# Microcontroller.net
KiCad netlist of a schematic drawn in Altium Designer
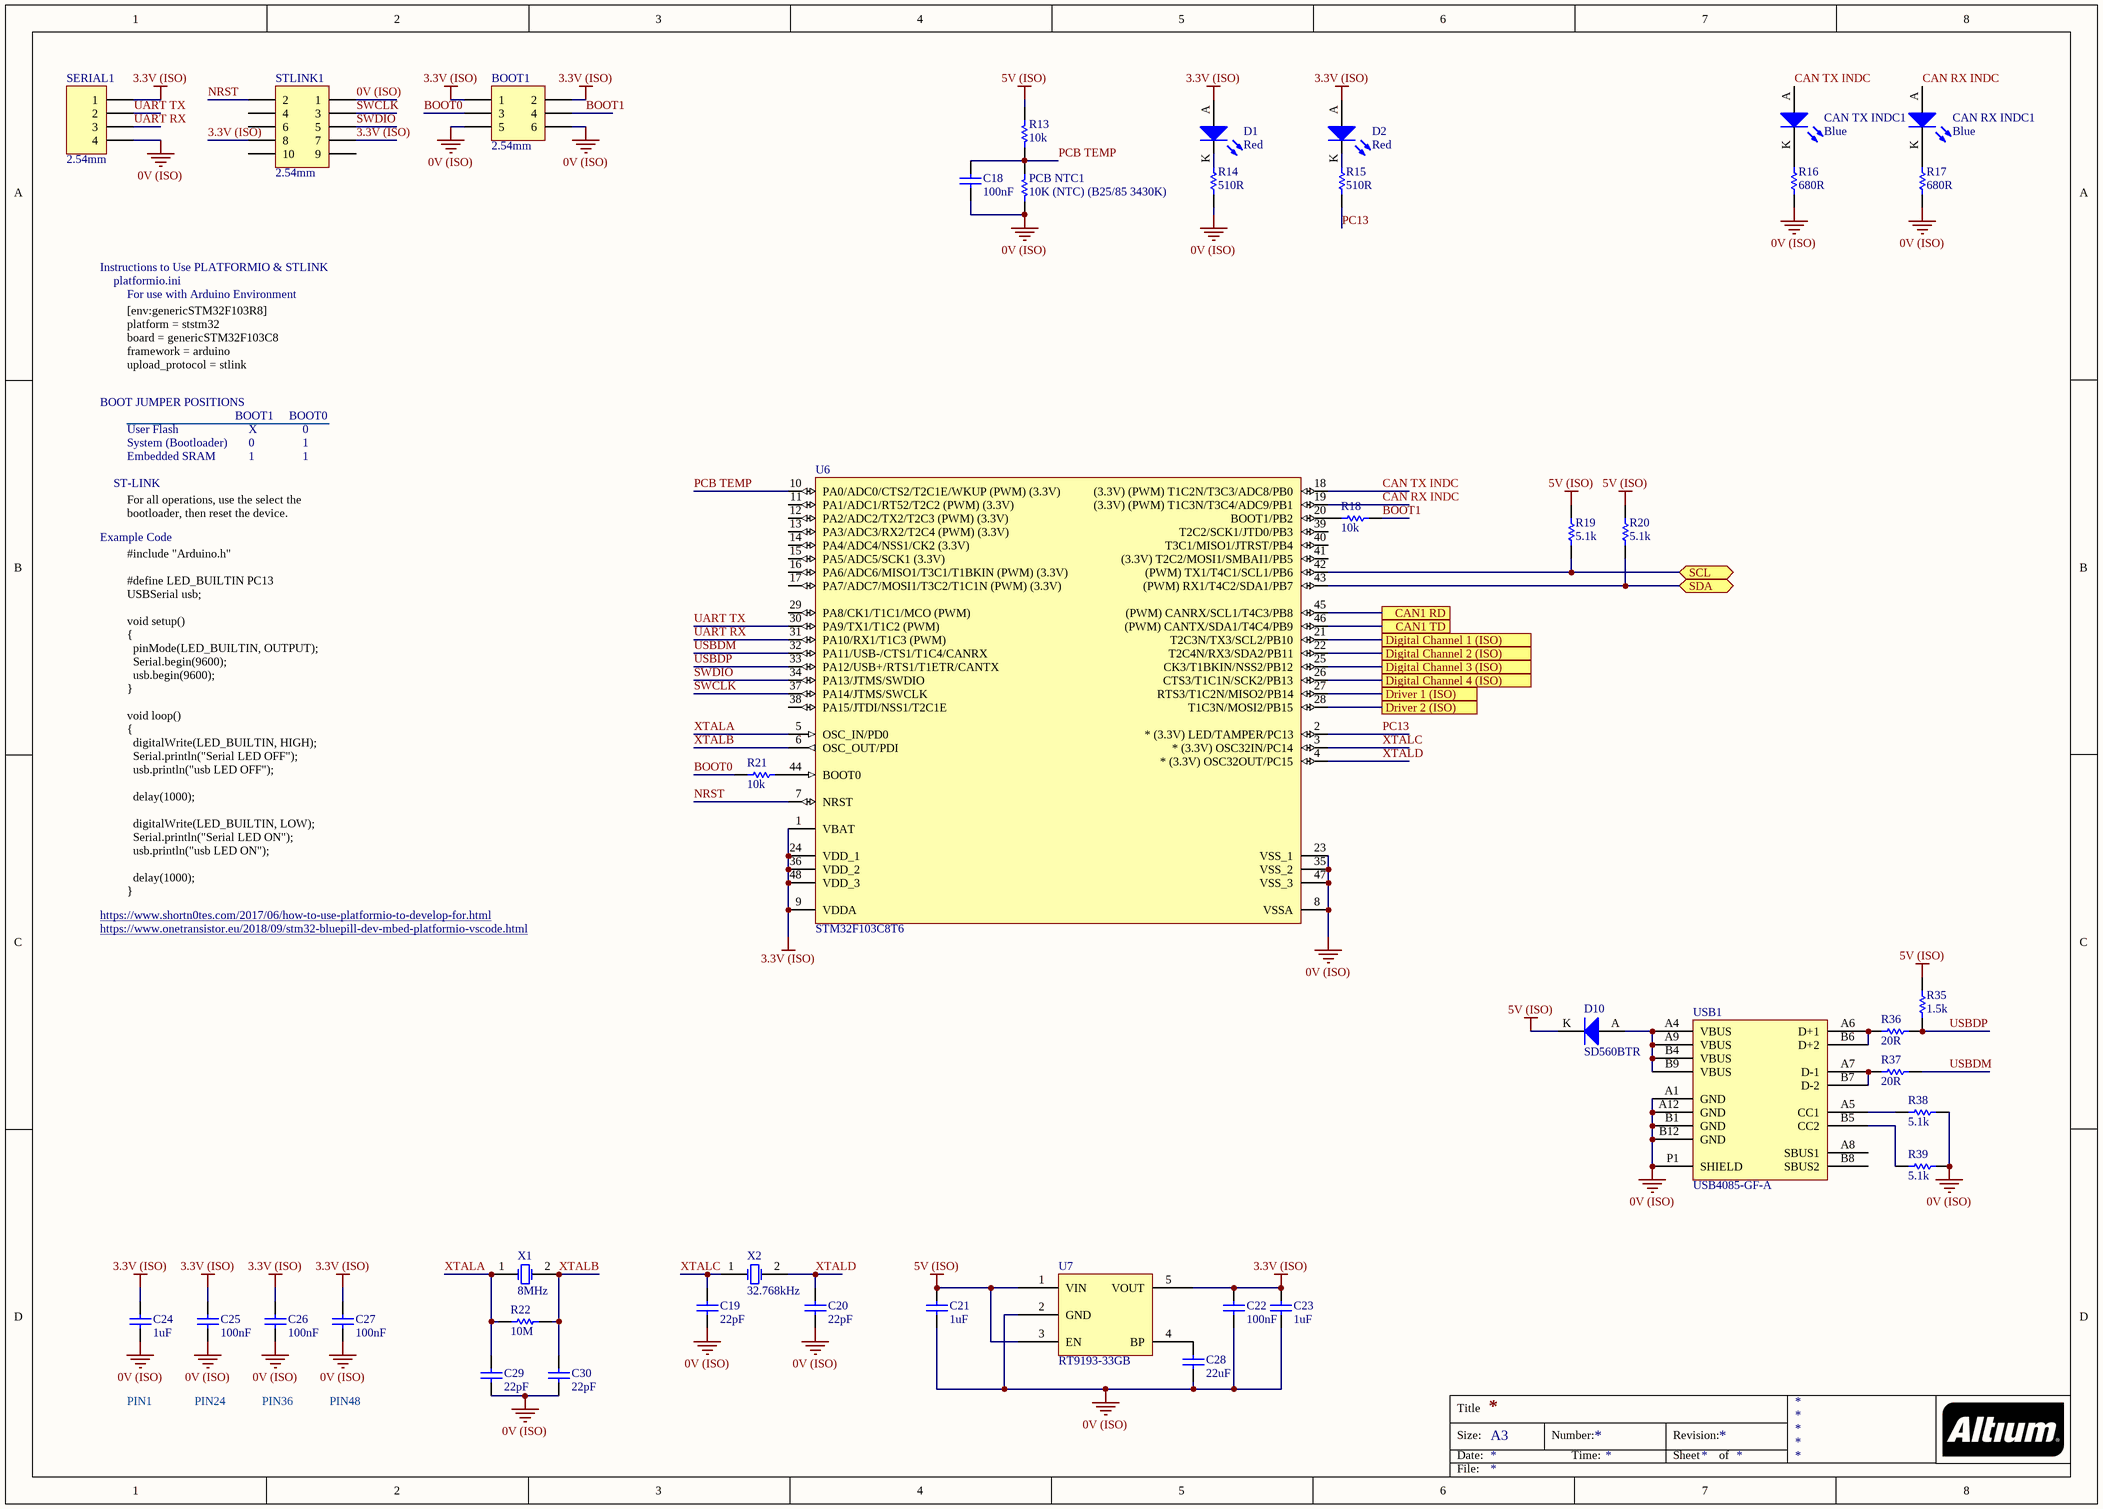
[diagram p0: Microcontroller.SchDoc]

(export (version "E")
  (design (tool "Eeschema 10.0.6"))
  (components
    (comp (ref "BOOT1")
      (value "2.54mm")
      (footprint "TH 2.54mm Header 2x3")
      (fields (field (name "PART NUMBER") "TH 2.54mm Header 2x3") (field (name "CONTACT") "NA"))
      (libsource (lib "ts_20-standard-connectors") (part "Header 2x3"))
    )
    (comp (ref "C18")
      (value "100nF")
      (footprint "0805")
      (fields
        (field (name "PART NUMBER") "GCM21BR71E104KA37L")
        (field (name "TOLERANCE") "10%")
        (field (name "MANUFACTURER") "muRata")
      )
      (libsource (lib "ts_20-standard-library") (part "Capacitor"))
    )
    (comp (ref "C19")
      (value "22pF")
      (footprint "0805")
      (fields
        (field (name "PART NUMBER") "GCM21B5C1H220JA37L")
        (field (name "TOLERANCE") "5%")
        (field (name "MANUFACTURER") "muRata")
      )
      (libsource (lib "ts_20-standard-library") (part "Capacitor"))
    )
    (comp (ref "C20")
      (value "22pF")
      (footprint "0805")
      (fields
        (field (name "PART NUMBER") "GCM21B5C1H220JA37L")
        (field (name "TOLERANCE") "5%")
        (field (name "MANUFACTURER") "muRata")
      )
      (libsource (lib "ts_20-standard-library") (part "Capacitor"))
    )
    (comp (ref "C21")
      (value "1uF")
      (footprint "0805")
      (fields
        (field (name "PART NUMBER") "AC0805KKX7R8BB105")
        (field (name "TOLERANCE") "10%")
        (field (name "MANUFACTURER") "YAGEO")
      )
      (libsource (lib "ts_20-standard-library") (part "Capacitor"))
    )
    (comp (ref "C22")
      (value "100nF")
      (footprint "0805")
      (fields
        (field (name "PART NUMBER") "GCM21BR71E104KA37L")
        (field (name "TOLERANCE") "10%")
        (field (name "MANUFACTURER") "muRata")
      )
      (libsource (lib "ts_20-standard-library") (part "Capacitor"))
    )
    (comp (ref "C23")
      (value "1uF")
      (footprint "0805")
      (fields
        (field (name "PART NUMBER") "AC0805KKX7R8BB105")
        (field (name "TOLERANCE") "10%")
        (field (name "MANUFACTURER") "YAGEO")
      )
      (libsource (lib "ts_20-standard-library") (part "Capacitor"))
    )
    (comp (ref "C24")
      (value "1uF")
      (footprint "0805")
      (fields
        (field (name "PART NUMBER") "AC0805KKX7R8BB105")
        (field (name "TOLERANCE") "10%")
        (field (name "MANUFACTURER") "YAGEO")
      )
      (libsource (lib "ts_20-standard-library") (part "Capacitor"))
    )
    (comp (ref "C25")
      (value "100nF")
      (footprint "0805")
      (fields
        (field (name "PART NUMBER") "GCM21BR71E104KA37L")
        (field (name "TOLERANCE") "10%")
        (field (name "MANUFACTURER") "muRata")
      )
      (libsource (lib "ts_20-standard-library") (part "Capacitor"))
    )
    (comp (ref "C26")
      (value "100nF")
      (footprint "0805")
      (fields
        (field (name "PART NUMBER") "GCM21BR71E104KA37L")
        (field (name "TOLERANCE") "10%")
        (field (name "MANUFACTURER") "muRata")
      )
      (libsource (lib "ts_20-standard-library") (part "Capacitor"))
    )
    (comp (ref "C27")
      (value "100nF")
      (footprint "0805")
      (fields
        (field (name "PART NUMBER") "GCM21BR71E104KA37L")
        (field (name "TOLERANCE") "10%")
        (field (name "MANUFACTURER") "muRata")
      )
      (libsource (lib "ts_20-standard-library") (part "Capacitor"))
    )
    (comp (ref "C28")
      (value "22uF")
      (footprint "0805")
      (fields
        (field (name "PART NUMBER") "GRM21BR61A226ME51L")
        (field (name "TOLERANCE") "20%")
        (field (name "MANUFACTURER") "muRata")
      )
      (libsource (lib "ts_20-standard-library") (part "Capacitor"))
    )
    (comp (ref "C29")
      (value "22pF")
      (footprint "0805")
      (fields
        (field (name "PART NUMBER") "GCM21B5C1H220JA37L")
        (field (name "TOLERANCE") "5%")
        (field (name "MANUFACTURER") "muRata")
      )
      (libsource (lib "ts_20-standard-library") (part "Capacitor"))
    )
    (comp (ref "C30")
      (value "22pF")
      (footprint "0805")
      (fields
        (field (name "PART NUMBER") "GCM21B5C1H220JA37L")
        (field (name "TOLERANCE") "5%")
        (field (name "MANUFACTURER") "muRata")
      )
      (libsource (lib "ts_20-standard-library") (part "Capacitor"))
    )
    (comp (ref "CAN RX INDC1")
      (value "Blue")
      (footprint "0805 LED")
      (description "LED BLUE CLEAR 2012 SMD")
      (fields
        (field (name "PART NUMBER") "SML-MN2BCTT86C")
        (field (name "MANUFACTURER") "ROHM Semiconductor")
      )
      (libsource (lib "ts_20-standard-library") (part "LED"))
    )
    (comp (ref "CAN TX INDC1")
      (value "Blue")
      (footprint "0805 LED")
      (description "LED BLUE CLEAR 2012 SMD")
      (fields
        (field (name "PART NUMBER") "SML-MN2BCTT86C")
        (field (name "MANUFACTURER") "ROHM Semiconductor")
      )
      (libsource (lib "ts_20-standard-library") (part "LED"))
    )
    (comp (ref "D1")
      (value "Red")
      (footprint "0805 LED")
      (description "Red LED Indication - Discrete 1.75V 0805 (2012 Metric)")
      (fields (field (name "MANUFACTURER") "ROHM Semiconductor") (field (name "PART NUMBER") "SML-210LTT86"))
      (libsource (lib "ts_20-standard-library") (part "LED"))
    )
    (comp (ref "D2")
      (value "Red")
      (footprint "0805 LED")
      (description "Red LED Indication - Discrete 1.75V 0805 (2012 Metric)")
      (fields (field (name "MANUFACTURER") "ROHM Semiconductor") (field (name "PART NUMBER") "SML-210LTT86"))
      (libsource (lib "ts_20-standard-library") (part "LED"))
    )
    (comp (ref "D10")
      (value "SD560BTR")
      (footprint "SMB Diode")
      (description "1.2V_F 600V 5A SMB")
      (fields
        (field (name "MANUFACTURER") "SMC Diode Solutions")
        (field (name "DIGIKEY PART NUMBER") "1655-1530-2-ND")
      )
      (libsource (lib "ts_20-standard-library") (part "Diode"))
    )
    (comp (ref "PCB NTC1")
      (value "10K (NTC) (B25/85 3430K)")
      (footprint "0805")
      (fields
        (field (name "PART NUMBER") "NTCS0805E3103FLT")
        (field (name "MANUFACTURER") "Vishay Beyschlag")
        (field (name "TOLERANCE") "0.01")
      )
      (libsource (lib "ts_20-standard-library") (part "Resistor"))
    )
    (comp (ref "R13")
      (value "10k")
      (footprint "0805")
      (fields
        (field (name "PART NUMBER") "RC0805FR0710KL")
        (field (name "MANUFACTURER") "YAGEO")
        (field (name "TOLERANCE") "0.01")
      )
      (libsource (lib "ts_20-standard-library") (part "Resistor"))
    )
    (comp (ref "R14")
      (value "510R")
      (footprint "0805")
      (fields
        (field (name "MANUFACTURER") "YAGEO")
        (field (name "PART NUMBER") "RC0805FR07510RL")
        (field (name "TOLERANCE") "0.01")
      )
      (libsource (lib "ts_20-standard-library") (part "Resistor"))
    )
    (comp (ref "R15")
      (value "510R")
      (footprint "0805")
      (fields
        (field (name "MANUFACTURER") "YAGEO")
        (field (name "PART NUMBER") "RC0805FR07510RL")
        (field (name "TOLERANCE") "0.01")
      )
      (libsource (lib "ts_20-standard-library") (part "Resistor"))
    )
    (comp (ref "R16")
      (value "680R")
      (footprint "0805")
      (fields
        (field (name "PART NUMBER") "RC0805FR07680RL")
        (field (name "MANUFACTURER") "YAGEO")
        (field (name "TOLERANCE") "0.01")
      )
      (libsource (lib "ts_20-standard-library") (part "Resistor"))
    )
    (comp (ref "R17")
      (value "680R")
      (footprint "0805")
      (fields
        (field (name "PART NUMBER") "RC0805FR07680RL")
        (field (name "MANUFACTURER") "YAGEO")
        (field (name "TOLERANCE") "0.01")
      )
      (libsource (lib "ts_20-standard-library") (part "Resistor"))
    )
    (comp (ref "R18")
      (value "10k")
      (footprint "0805")
      (fields
        (field (name "PART NUMBER") "RC0805FR0710KL")
        (field (name "MANUFACTURER") "YAGEO")
        (field (name "TOLERANCE") "0.01")
      )
      (libsource (lib "ts_20-standard-library") (part "Resistor"))
    )
    (comp (ref "R19")
      (value "5.1k")
      (footprint "0805")
      (fields
        (field (name "PART NUMBER") "RC0805FR075K1L")
        (field (name "MANUFACTURER") "YAGEO")
        (field (name "TOLERANCE") "0.01")
      )
      (libsource (lib "ts_20-standard-library") (part "Resistor"))
    )
    (comp (ref "R20")
      (value "5.1k")
      (footprint "0805")
      (fields
        (field (name "PART NUMBER") "RC0805FR075K1L")
        (field (name "MANUFACTURER") "YAGEO")
        (field (name "TOLERANCE") "0.01")
      )
      (libsource (lib "ts_20-standard-library") (part "Resistor"))
    )
    (comp (ref "R21")
      (value "10k")
      (footprint "0805")
      (fields
        (field (name "PART NUMBER") "RC0805FR0710KL")
        (field (name "MANUFACTURER") "YAGEO")
        (field (name "TOLERANCE") "0.01")
      )
      (libsource (lib "ts_20-standard-library") (part "Resistor"))
    )
    (comp (ref "R22")
      (value "10M")
      (footprint "0805")
      (fields
        (field (name "PART NUMBER") "RC0805FR0710ML")
        (field (name "MANUFACTURER") "YAGEO")
        (field (name "TOLERANCE") "0.01")
      )
      (libsource (lib "ts_20-standard-library") (part "Resistor"))
    )
    (comp (ref "R35")
      (value "1.5k")
      (footprint "0805")
      (fields
        (field (name "PART NUMBER") "RC0805FR071K5L")
        (field (name "MANUFACTURER") "YAGEO")
        (field (name "TOLERANCE") "0.01")
      )
      (libsource (lib "ts_20-standard-library") (part "Resistor"))
    )
    (comp (ref "R36")
      (value "20R")
      (footprint "0805")
      (fields
        (field (name "PART NUMBER") "RC0805FR0720RL")
        (field (name "MANUFACTURER") "YAGEO")
        (field (name "TOLERANCE") "0.01")
      )
      (libsource (lib "ts_20-standard-library") (part "Resistor"))
    )
    (comp (ref "R37")
      (value "20R")
      (footprint "0805")
      (fields
        (field (name "PART NUMBER") "RC0805FR0720RL")
        (field (name "MANUFACTURER") "YAGEO")
        (field (name "TOLERANCE") "0.01")
      )
      (libsource (lib "ts_20-standard-library") (part "Resistor"))
    )
    (comp (ref "R38")
      (value "5.1k")
      (footprint "0805")
      (fields
        (field (name "PART NUMBER") "RC0805FR075K1L")
        (field (name "MANUFACTURER") "YAGEO")
        (field (name "TOLERANCE") "0.01")
      )
      (libsource (lib "ts_20-standard-library") (part "Resistor"))
    )
    (comp (ref "R39")
      (value "5.1k")
      (footprint "0805")
      (fields
        (field (name "PART NUMBER") "RC0805FR075K1L")
        (field (name "MANUFACTURER") "YAGEO")
        (field (name "TOLERANCE") "0.01")
      )
      (libsource (lib "ts_20-standard-library") (part "Resistor"))
    )
    (comp (ref "SERIAL1")
      (value "2.54mm")
      (footprint "TH 2.54mm Header 1x4")
      (fields (field (name "PART NUMBER") "TH 2.54mm Header 1x4") (field (name "CONTACT") "NA"))
      (libsource (lib "ts_20-standard-connectors") (part "Header 1x4"))
    )
    (comp (ref "STLINK1")
      (value "2.54mm")
      (footprint "TH 2.54mm Header 2x5")
      (fields (field (name "PART NUMBER") "TH 2.54mm Header 2x5") (field (name "CONTACT") "NA"))
      (libsource (lib "ts_20-standard-connectors") (part "Header 2x5"))
    )
    (comp (ref "U6")
      (value "STM32F103C8T6")
      (footprint "STM 48-LQFP")
      (description "ARM® Cortex®-M3 STM32F1 Microcontroller IC 32-Bit 72MHz 64KB (64K x 8) FLASH")
      (fields
        (field (name "MANUFACTURER") "STMicroelectronics")
        (field (name "DIGIKEY PART NUMBER") "497-6063-ND")
      )
      (libsource (lib "ts_20-standard-library") (part "STM32F103C8T6"))
    )
    (comp (ref "U7")
      (value "RT9193-33GB")
      (footprint "RICHTEK SOT-23-5")
      (description "IC REG LINEAR 3.3V 300MA SOT23-5")
      (fields (field (name "MANUFACTURER") "Richtek") (field (name "DIGIKEY PART NUMBER") "1028-1014-1-ND"))
      (libsource (lib "ts_20-standard-library") (part "RT9193-33GB"))
    )
    (comp (ref "USB1")
      (value "USB4085-GF-A")
      (footprint "USB4085-GF-A")
      (description "USB - C (Type - C) USB 2.0 Receptacle Connector 16 Position Through Hole, Right Angle")
      (fields (field (name "DIGIKEY PART NUMBER") "2073-USB4085-GF-ACT-ND"))
      (libsource (lib "ts_20-standard-connectors") (part "USB4085-GF-A"))
    )
    (comp (ref "X1")
      (value "8MHz")
      (footprint "Abracon HC-49/US")
      (fields
        (field (name "PART NUMBER") "ABLS-8.000MHZ-B4-T")
        (field (name "MANUFACTURER") "Abracon LLC")
        (field (name "DIGIKEY PART NUMBER") "535-10212-2-ND")
      )
      (libsource (lib "ts_20-standard-library") (part "Crystal"))
    )
    (comp (ref "X2")
      (value "32.768kHz")
      (footprint "EPSON 2-SMD")
      (fields
        (field (name "PART NUMBER") "FC-135 32.7680KA-A5")
        (field (name "MANUFACTURER") "EPSON")
        (field (name "DIGIKEY PART NUMBER") "SER4103TR-ND")
      )
      (libsource (lib "ts_20-standard-library") (part "Crystal"))
    )
  )
  (nets
    (net (code "1") (name "/BOOT0") (class "Default")
      (node (ref "BOOT1") (pin "3") (pinfunction "3_3") (pintype "passive"))
      (node (ref "R21") (pin "1") (pinfunction "1_1") (pintype "passive"))
    )
    (net (code "2") (name "/BOOT1") (class "Default")
      (node (ref "BOOT1") (pin "4") (pinfunction "4_4") (pintype "passive"))
      (node (ref "R18") (pin "2") (pinfunction "2_2") (pintype "passive"))
    )
    (net (code "3") (name "/CAN RX INDC") (class "Default")
      (node (ref "CAN RX INDC1") (pin "A") (pinfunction "A_A") (pintype "passive"))
      (node (ref "U6") (pin "19") (pinfunction "(3.3V)_(PWM)_T1C3N/T3C4/ADC9/PB1_19") (pintype "bidirectional"))
    )
    (net (code "4") (name "/CAN TX INDC") (class "Default")
      (node (ref "CAN TX INDC1") (pin "A") (pinfunction "A_A") (pintype "passive"))
      (node (ref "U6") (pin "18") (pinfunction "(3.3V)_(PWM)_T1C2N/T3C3/ADC8/PB0_18") (pintype "bidirectional"))
    )
    (net (code "5") (name "/CAN1 RD") (class "Default")
      (node (ref "U6") (pin "45") (pinfunction "(PWM)_CANRX/SCL1/T4C3/PB8_45") (pintype "bidirectional"))
    )
    (net (code "6") (name "/CAN1 TD") (class "Default")
      (node (ref "U6") (pin "46") (pinfunction "(PWM)_CANTX/SDA1/T4C4/PB9_46") (pintype "bidirectional"))
    )
    (net (code "7") (name "/Digital Channel 1 (ISO)") (class "Default")
      (node (ref "U6") (pin "21") (pinfunction "T2C3N/TX3/SCL2/PB10_21") (pintype "bidirectional"))
    )
    (net (code "8") (name "/Digital Channel 2 (ISO)") (class "Default")
      (node (ref "U6") (pin "22") (pinfunction "T2C4N/RX3/SDA2/PB11_22") (pintype "bidirectional"))
    )
    (net (code "9") (name "/Digital Channel 3 (ISO)") (class "Default")
      (node (ref "U6") (pin "25") (pinfunction "CK3/T1BKIN/NSS2/PB12_25") (pintype "bidirectional"))
    )
    (net (code "10") (name "/Digital Channel 4 (ISO)") (class "Default")
      (node (ref "U6") (pin "26") (pinfunction "CTS3/T1C1N/SCK2/PB13_26") (pintype "bidirectional"))
    )
    (net (code "11") (name "/Driver 1 (ISO)") (class "Default")
      (node (ref "U6") (pin "27") (pinfunction "RTS3/T1C2N/MISO2/PB14_27") (pintype "bidirectional"))
    )
    (net (code "12") (name "/Driver 2 (ISO)") (class "Default")
      (node (ref "U6") (pin "28") (pinfunction "T1C3N/MOSI2/PB15_28") (pintype "bidirectional"))
    )
    (net (code "13") (name "/NRST") (class "Default")
      (node (ref "STLINK1") (pin "2") (pinfunction "2_2") (pintype "passive"))
      (node (ref "U6") (pin "7") (pinfunction "NRST_7") (pintype "bidirectional"))
    )
    (net (code "14") (name "/PC13") (class "Default")
      (node (ref "R15") (pin "1") (pinfunction "1_1") (pintype "passive"))
      (node (ref "U6") (pin "2") (pinfunction "*_(3.3V)_LED/TAMPER/PC13_2") (pintype "bidirectional"))
    )
    (net (code "15") (name "/PCB TEMP") (class "Default")
      (node (ref "C18") (pin "2") (pinfunction "2_2") (pintype "passive"))
      (node (ref "PCB NTC1") (pin "2") (pinfunction "2_2") (pintype "passive"))
      (node (ref "R13") (pin "1") (pinfunction "1_1") (pintype "passive"))
      (node (ref "U6") (pin "10") (pinfunction "PA0/ADC0/CTS2/T2C1E/WKUP_(PWM)_(3.3V)_10") (pintype "bidirectional"))
    )
    (net (code "16") (name "/SCL") (class "Default")
      (node (ref "R19") (pin "1") (pinfunction "1_1") (pintype "passive"))
      (node (ref "U6") (pin "42") (pinfunction "(PWM)_TX1/T4C1/SCL1/PB6_42") (pintype "bidirectional"))
    )
    (net (code "17") (name "/SDA") (class "Default")
      (node (ref "R20") (pin "1") (pinfunction "1_1") (pintype "passive"))
      (node (ref "U6") (pin "43") (pinfunction "(PWM)_RX1/T4C2/SDA1/PB7_43") (pintype "bidirectional"))
    )
    (net (code "18") (name "/SWCLK") (class "Default")
      (node (ref "STLINK1") (pin "3") (pinfunction "3_3") (pintype "passive"))
      (node (ref "U6") (pin "37") (pinfunction "PA14/JTMS/SWCLK_37") (pintype "bidirectional"))
    )
    (net (code "19") (name "/SWDIO") (class "Default")
      (node (ref "STLINK1") (pin "5") (pinfunction "5_5") (pintype "passive"))
      (node (ref "U6") (pin "34") (pinfunction "PA13/JTMS/SWDIO_34") (pintype "bidirectional"))
    )
    (net (code "20") (name "/UART RX") (class "Default")
      (node (ref "SERIAL1") (pin "3") (pinfunction "3_3") (pintype "passive"))
      (node (ref "U6") (pin "31") (pinfunction "PA10/RX1/T1C3_(PWM)_31") (pintype "bidirectional"))
    )
    (net (code "21") (name "/UART TX") (class "Default")
      (node (ref "SERIAL1") (pin "2") (pinfunction "2_2") (pintype "passive"))
      (node (ref "U6") (pin "30") (pinfunction "PA9/TX1/T1C2_(PWM)_30") (pintype "bidirectional"))
    )
    (net (code "22") (name "/USBDM") (class "Default")
      (node (ref "R37") (pin "2") (pinfunction "2_2") (pintype "passive"))
      (node (ref "U6") (pin "32") (pinfunction "PA11/USB-/CTS1/T1C4/CANRX_32") (pintype "bidirectional"))
    )
    (net (code "23") (name "/USBDP") (class "Default")
      (node (ref "R35") (pin "1") (pinfunction "1_1") (pintype "passive"))
      (node (ref "R36") (pin "2") (pinfunction "2_2") (pintype "passive"))
      (node (ref "U6") (pin "33") (pinfunction "PA12/USB+/RTS1/T1ETR/CANTX_33") (pintype "bidirectional"))
    )
    (net (code "24") (name "/XTALA") (class "Default")
      (node (ref "C29") (pin "2") (pinfunction "2_2") (pintype "passive"))
      (node (ref "R22") (pin "2") (pinfunction "2_2") (pintype "passive"))
      (node (ref "U6") (pin "5") (pinfunction "OSC_IN/PD0_5") (pintype "input"))
      (node (ref "X1") (pin "1") (pinfunction "OSC1_1") (pintype "passive"))
    )
    (net (code "25") (name "/XTALB") (class "Default")
      (node (ref "C30") (pin "2") (pinfunction "2_2") (pintype "passive"))
      (node (ref "R22") (pin "1") (pinfunction "1_1") (pintype "passive"))
      (node (ref "U6") (pin "6") (pinfunction "OSC_OUT/PDI_6") (pintype "output"))
      (node (ref "X1") (pin "2") (pinfunction "OSC2_2") (pintype "passive"))
    )
    (net (code "26") (name "/XTALC") (class "Default")
      (node (ref "C19") (pin "2") (pinfunction "2_2") (pintype "passive"))
      (node (ref "U6") (pin "3") (pinfunction "*_(3.3V)_OSC32IN/PC14_3") (pintype "bidirectional"))
      (node (ref "X2") (pin "1") (pinfunction "OSC1_1") (pintype "passive"))
    )
    (net (code "27") (name "/XTALD") (class "Default")
      (node (ref "C20") (pin "2") (pinfunction "2_2") (pintype "passive"))
      (node (ref "U6") (pin "4") (pinfunction "*_(3.3V)_OSC32OUT/PC15_4") (pintype "bidirectional"))
      (node (ref "X2") (pin "2") (pinfunction "OSC2_2") (pintype "passive"))
    )
    (net (code "28") (name "0V (ISO)") (class "Default")
      (node (ref "BOOT1") (pin "5") (pinfunction "5_5") (pintype "passive"))
      (node (ref "BOOT1") (pin "6") (pinfunction "6_6") (pintype "passive"))
      (node (ref "C18") (pin "1") (pinfunction "1_1") (pintype "passive"))
      (node (ref "C19") (pin "1") (pinfunction "1_1") (pintype "passive"))
      (node (ref "C20") (pin "1") (pinfunction "1_1") (pintype "passive"))
      (node (ref "C21") (pin "1") (pinfunction "1_1") (pintype "passive"))
      (node (ref "C22") (pin "1") (pinfunction "1_1") (pintype "passive"))
      (node (ref "C23") (pin "1") (pinfunction "1_1") (pintype "passive"))
      (node (ref "C24") (pin "1") (pinfunction "1_1") (pintype "passive"))
      (node (ref "C25") (pin "1") (pinfunction "1_1") (pintype "passive"))
      (node (ref "C26") (pin "1") (pinfunction "1_1") (pintype "passive"))
      (node (ref "C27") (pin "1") (pinfunction "1_1") (pintype "passive"))
      (node (ref "C28") (pin "1") (pinfunction "1_1") (pintype "passive"))
      (node (ref "C29") (pin "1") (pinfunction "1_1") (pintype "passive"))
      (node (ref "C30") (pin "1") (pinfunction "1_1") (pintype "passive"))
      (node (ref "PCB NTC1") (pin "1") (pinfunction "1_1") (pintype "passive"))
      (node (ref "R14") (pin "1") (pinfunction "1_1") (pintype "passive"))
      (node (ref "R16") (pin "1") (pinfunction "1_1") (pintype "passive"))
      (node (ref "R17") (pin "1") (pinfunction "1_1") (pintype "passive"))
      (node (ref "R38") (pin "2") (pinfunction "2_2") (pintype "passive"))
      (node (ref "R39") (pin "2") (pinfunction "2_2") (pintype "passive"))
      (node (ref "SERIAL1") (pin "4") (pinfunction "4_4") (pintype "passive"))
      (node (ref "STLINK1") (pin "1") (pinfunction "1_1") (pintype "passive"))
      (node (ref "U6") (pin "23") (pinfunction "VSS_1_23") (pintype "power_in"))
      (node (ref "U6") (pin "35") (pinfunction "VSS_2_35") (pintype "power_in"))
      (node (ref "U6") (pin "47") (pinfunction "VSS_3_47") (pintype "power_in"))
      (node (ref "U6") (pin "8") (pinfunction "VSSA_8") (pintype "power_in"))
      (node (ref "U7") (pin "2") (pinfunction "GND_2") (pintype "passive"))
      (node (ref "USB1") (pin "A1") (pinfunction "GND_A1") (pintype "passive"))
      (node (ref "USB1") (pin "A12") (pinfunction "GND_A12") (pintype "passive"))
      (node (ref "USB1") (pin "B1") (pinfunction "GND_B1") (pintype "passive"))
      (node (ref "USB1") (pin "B12") (pinfunction "GND_B12") (pintype "passive"))
      (node (ref "USB1") (pin "P1") (pinfunction "SHIELD_P1") (pintype "passive"))
    )
    (net (code "29") (name "3.3V (ISO)") (class "Default")
      (node (ref "BOOT1") (pin "1") (pinfunction "1_1") (pintype "passive"))
      (node (ref "BOOT1") (pin "2") (pinfunction "2_2") (pintype "passive"))
      (node (ref "C22") (pin "2") (pinfunction "2_2") (pintype "passive"))
      (node (ref "C23") (pin "2") (pinfunction "2_2") (pintype "passive"))
      (node (ref "C24") (pin "2") (pinfunction "2_2") (pintype "passive"))
      (node (ref "C25") (pin "2") (pinfunction "2_2") (pintype "passive"))
      (node (ref "C26") (pin "2") (pinfunction "2_2") (pintype "passive"))
      (node (ref "C27") (pin "2") (pinfunction "2_2") (pintype "passive"))
      (node (ref "D1") (pin "A") (pinfunction "A_A") (pintype "passive"))
      (node (ref "D2") (pin "A") (pinfunction "A_A") (pintype "passive"))
      (node (ref "SERIAL1") (pin "1") (pinfunction "1_1") (pintype "passive"))
      (node (ref "STLINK1") (pin "7") (pinfunction "7_7") (pintype "passive"))
      (node (ref "STLINK1") (pin "8") (pinfunction "8_8") (pintype "passive"))
      (node (ref "U6") (pin "1") (pinfunction "VBAT_1") (pintype "power_in"))
      (node (ref "U6") (pin "24") (pinfunction "VDD_1_24") (pintype "power_in"))
      (node (ref "U6") (pin "36") (pinfunction "VDD_2_36") (pintype "power_in"))
      (node (ref "U6") (pin "48") (pinfunction "VDD_3_48") (pintype "power_in"))
      (node (ref "U6") (pin "9") (pinfunction "VDDA_9") (pintype "power_in"))
      (node (ref "U7") (pin "5") (pinfunction "VOUT_5") (pintype "passive"))
    )
    (net (code "30") (name "5V (ISO)") (class "Default")
      (node (ref "C21") (pin "2") (pinfunction "2_2") (pintype "passive"))
      (node (ref "D10") (pin "K") (pinfunction "K_K") (pintype "passive"))
      (node (ref "R13") (pin "2") (pinfunction "2_2") (pintype "passive"))
      (node (ref "R19") (pin "2") (pinfunction "2_2") (pintype "passive"))
      (node (ref "R20") (pin "2") (pinfunction "2_2") (pintype "passive"))
      (node (ref "R35") (pin "2") (pinfunction "2_2") (pintype "passive"))
      (node (ref "U7") (pin "1") (pinfunction "VIN_1") (pintype "passive"))
      (node (ref "U7") (pin "3") (pinfunction "EN_3") (pintype "passive"))
    )
    (net (code "31") (name "Net-(CAN RX INDC1-PadK)") (class "Default")
      (node (ref "CAN RX INDC1") (pin "K") (pinfunction "K_K") (pintype "passive"))
      (node (ref "R17") (pin "2") (pinfunction "2_2") (pintype "passive"))
    )
    (net (code "32") (name "Net-(CAN TX INDC1-PadK)") (class "Default")
      (node (ref "CAN TX INDC1") (pin "K") (pinfunction "K_K") (pintype "passive"))
      (node (ref "R16") (pin "2") (pinfunction "2_2") (pintype "passive"))
    )
    (net (code "33") (name "Net-(D1-PadK)") (class "Default")
      (node (ref "D1") (pin "K") (pinfunction "K_K") (pintype "passive"))
      (node (ref "R14") (pin "2") (pinfunction "2_2") (pintype "passive"))
    )
    (net (code "34") (name "Net-(D2-PadK)") (class "Default")
      (node (ref "D2") (pin "K") (pinfunction "K_K") (pintype "passive"))
      (node (ref "R15") (pin "2") (pinfunction "2_2") (pintype "passive"))
    )
    (net (code "35") (name "Net-(D10-PadA)") (class "Default")
      (node (ref "D10") (pin "A") (pinfunction "A_A") (pintype "passive"))
      (node (ref "USB1") (pin "A4") (pinfunction "VBUS_A4") (pintype "passive"))
      (node (ref "USB1") (pin "A9") (pinfunction "VBUS_A9") (pintype "passive"))
      (node (ref "USB1") (pin "B4") (pinfunction "VBUS_B4") (pintype "passive"))
      (node (ref "USB1") (pin "B9") (pinfunction "VBUS_B9") (pintype "passive"))
    )
    (net (code "36") (name "Net-(U6-BOOT0)") (class "Default")
      (node (ref "R21") (pin "2") (pinfunction "2_2") (pintype "passive"))
      (node (ref "U6") (pin "44") (pinfunction "BOOT0_44") (pintype "input"))
    )
    (net (code "37") (name "Net-(U6-BOOT1{slash}PB2)") (class "Default")
      (node (ref "R18") (pin "1") (pinfunction "1_1") (pintype "passive"))
      (node (ref "U6") (pin "20") (pinfunction "BOOT1/PB2_20") (pintype "bidirectional"))
    )
    (net (code "38") (name "Net-(U7-BP)") (class "Default")
      (node (ref "C28") (pin "2") (pinfunction "2_2") (pintype "passive"))
      (node (ref "U7") (pin "4") (pinfunction "BP_4") (pintype "passive"))
    )
    (net (code "39") (name "Net-(USB1-CC1)") (class "Default")
      (node (ref "R38") (pin "1") (pinfunction "1_1") (pintype "passive"))
      (node (ref "USB1") (pin "A5") (pinfunction "CC1_A5") (pintype "passive"))
    )
    (net (code "40") (name "Net-(USB1-CC2)") (class "Default")
      (node (ref "R39") (pin "1") (pinfunction "1_1") (pintype "passive"))
      (node (ref "USB1") (pin "B5") (pinfunction "CC2_B5") (pintype "passive"))
    )
    (net (code "41") (name "Net-(USB1-D+1)") (class "Default")
      (node (ref "R36") (pin "1") (pinfunction "1_1") (pintype "passive"))
      (node (ref "USB1") (pin "A6") (pinfunction "D+1_A6") (pintype "passive"))
      (node (ref "USB1") (pin "B6") (pinfunction "D+2_B6") (pintype "passive"))
    )
    (net (code "42") (name "Net-(USB1-D-1)") (class "Default")
      (node (ref "R37") (pin "1") (pinfunction "1_1") (pintype "passive"))
      (node (ref "USB1") (pin "A7") (pinfunction "D-1_A7") (pintype "passive"))
      (node (ref "USB1") (pin "B7") (pinfunction "D-2_B7") (pintype "passive"))
    )
    (net (code "43") (name "unconnected-(STLINK1-Pad4)") (class "Default")
      (node (ref "STLINK1") (pin "4") (pinfunction "4_4") (pintype "passive"))
    )
    (net (code "44") (name "unconnected-(STLINK1-Pad6)") (class "Default")
      (node (ref "STLINK1") (pin "6") (pinfunction "6_6") (pintype "passive"))
    )
    (net (code "45") (name "unconnected-(STLINK1-Pad9)") (class "Default")
      (node (ref "STLINK1") (pin "9") (pinfunction "9_9") (pintype "passive"))
    )
    (net (code "46") (name "unconnected-(STLINK1-Pad10)") (class "Default")
      (node (ref "STLINK1") (pin "10") (pinfunction "10_10") (pintype "passive"))
    )
    (net (code "47") (name "unconnected-(U6-(3.3V)_T2C2{slash}MOSI1{slash}SMBAI1{slash}PB5-Pad41)") (class "Default")
      (node (ref "U6") (pin "41") (pinfunction "(3.3V)_T2C2/MOSI1/SMBAI1/PB5_41") (pintype "bidirectional"))
    )
    (net (code "48") (name "unconnected-(U6-PA1{slash}ADC1{slash}RT52{slash}T2C2_(PWM)_(3.3V)-Pad11)") (class "Default")
      (node (ref "U6") (pin "11") (pinfunction "PA1/ADC1/RT52/T2C2_(PWM)_(3.3V)_11") (pintype "bidirectional"))
    )
    (net (code "49") (name "unconnected-(U6-PA2{slash}ADC2{slash}TX2{slash}T2C3_(PWM)_(3.3V)-Pad12)") (class "Default")
      (node (ref "U6") (pin "12") (pinfunction "PA2/ADC2/TX2/T2C3_(PWM)_(3.3V)_12") (pintype "bidirectional"))
    )
    (net (code "50") (name "unconnected-(U6-PA3{slash}ADC3{slash}RX2{slash}T2C4_(PWM)_(3.3V)-Pad13)") (class "Default")
      (node (ref "U6") (pin "13") (pinfunction "PA3/ADC3/RX2/T2C4_(PWM)_(3.3V)_13") (pintype "bidirectional"))
    )
    (net (code "51") (name "unconnected-(U6-PA4{slash}ADC4{slash}NSS1{slash}CK2_(3.3V)-Pad14)") (class "Default")
      (node (ref "U6") (pin "14") (pinfunction "PA4/ADC4/NSS1/CK2_(3.3V)_14") (pintype "bidirectional"))
    )
    (net (code "52") (name "unconnected-(U6-PA5{slash}ADC5{slash}SCK1_(3.3V)-Pad15)") (class "Default")
      (node (ref "U6") (pin "15") (pinfunction "PA5/ADC5/SCK1_(3.3V)_15") (pintype "bidirectional"))
    )
    (net (code "53") (name "unconnected-(U6-PA6{slash}ADC6{slash}MISO1{slash}T3C1{slash}T1BKIN_(PWM)_(3.3V)-Pad16)") (class "Default")
      (node (ref "U6") (pin "16") (pinfunction "PA6/ADC6/MISO1/T3C1/T1BKIN_(PWM)_(3.3V)_16") (pintype "bidirectional"))
    )
    (net (code "54") (name "unconnected-(U6-PA7{slash}ADC7{slash}MOSI1{slash}T3C2{slash}T1C1N_(PWM)_(3.3V)-Pad17)") (class "Default")
      (node (ref "U6") (pin "17") (pinfunction "PA7/ADC7/MOSI1/T3C2/T1C1N_(PWM)_(3.3V)_17") (pintype "bidirectional"))
    )
    (net (code "55") (name "unconnected-(U6-PA8{slash}CK1{slash}T1C1{slash}MCO_(PWM)-Pad29)") (class "Default")
      (node (ref "U6") (pin "29") (pinfunction "PA8/CK1/T1C1/MCO_(PWM)_29") (pintype "bidirectional"))
    )
    (net (code "56") (name "unconnected-(U6-PA15{slash}JTDI{slash}NSS1{slash}T2C1E-Pad38)") (class "Default")
      (node (ref "U6") (pin "38") (pinfunction "PA15/JTDI/NSS1/T2C1E_38") (pintype "bidirectional"))
    )
    (net (code "57") (name "unconnected-(U6-T2C2{slash}SCK1{slash}JTD0{slash}PB3-Pad39)") (class "Default")
      (node (ref "U6") (pin "39") (pinfunction "T2C2/SCK1/JTD0/PB3_39") (pintype "bidirectional"))
    )
    (net (code "58") (name "unconnected-(U6-T3C1{slash}MISO1{slash}JTRST{slash}PB4-Pad40)") (class "Default")
      (node (ref "U6") (pin "40") (pinfunction "T3C1/MISO1/JTRST/PB4_40") (pintype "bidirectional"))
    )
    (net (code "59") (name "unconnected-(USB1-SBUS1-PadA8)") (class "Default")
      (node (ref "USB1") (pin "A8") (pinfunction "SBUS1_A8") (pintype "passive"))
    )
    (net (code "60") (name "unconnected-(USB1-SBUS2-PadB8)") (class "Default")
      (node (ref "USB1") (pin "B8") (pinfunction "SBUS2_B8") (pintype "passive"))
    )
  )
)
